# amp_v2.net
KiCad netlist of a schematic drawn in Altium Designer
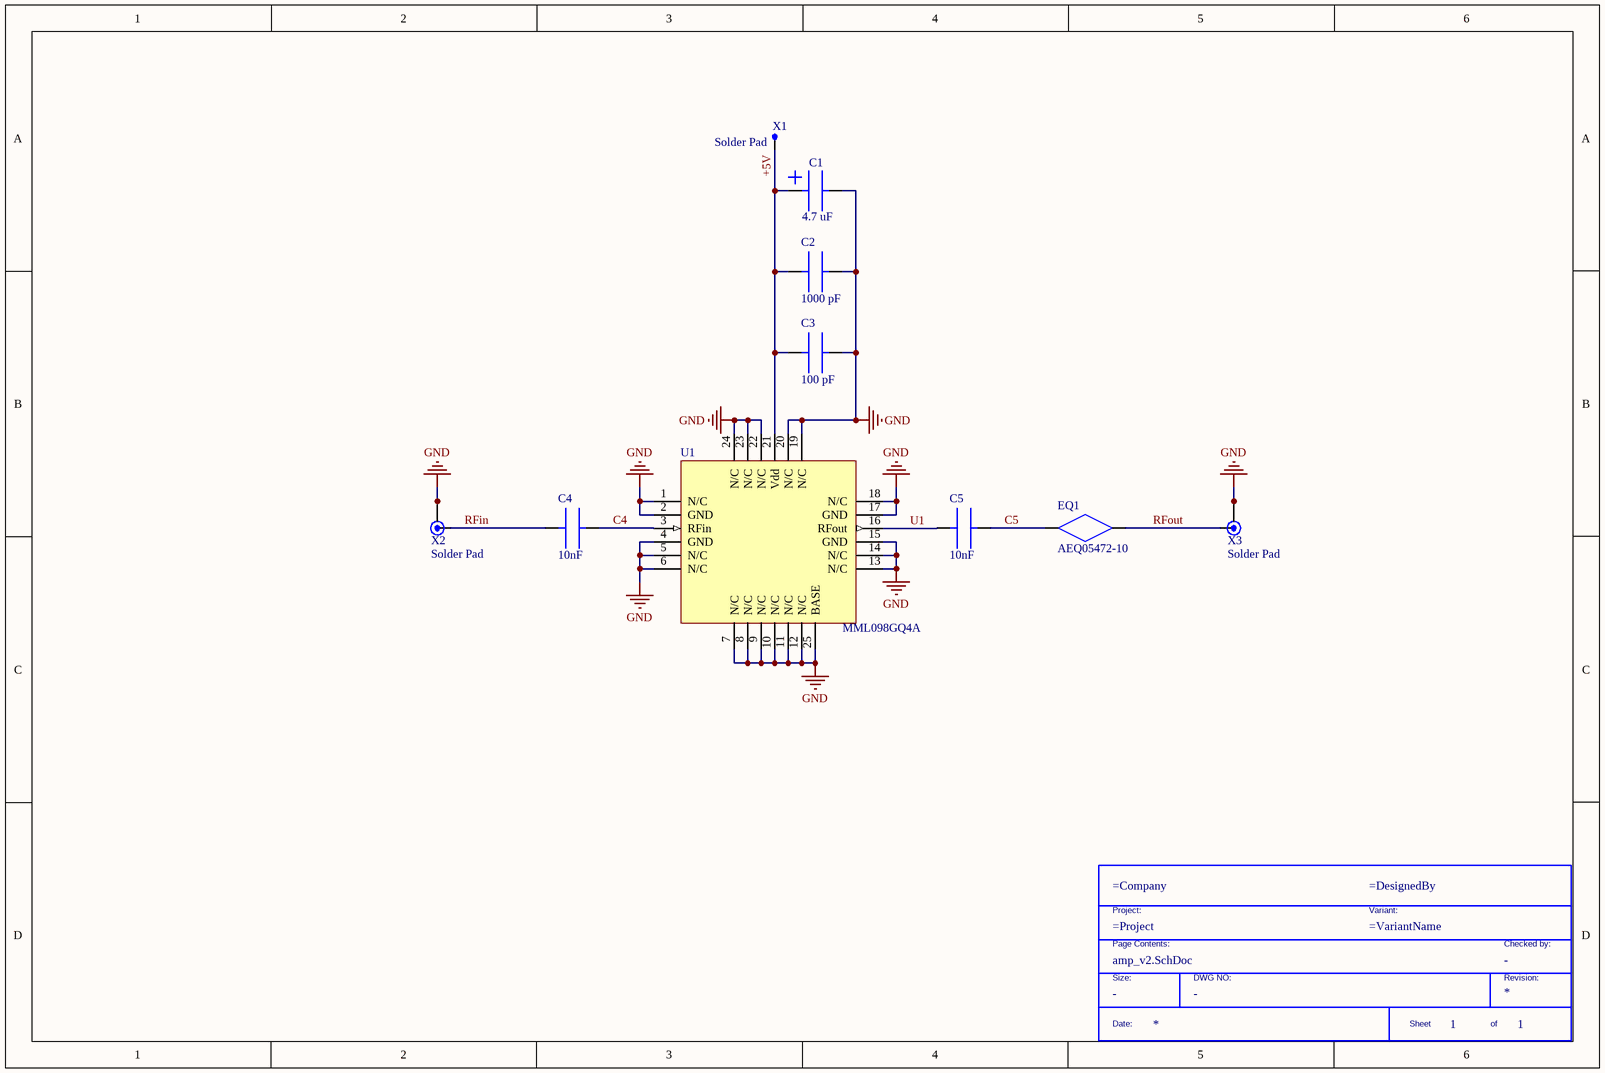
[diagram p0: amp_v2.SchDoc]

(export (version "E")
  (design (tool "Eeschema 10.0.6"))
  (components
    (comp (ref "*")
      (value "TitleBlock")
      (description "Standard Title Block")
      (fields (field (name "DWG NO") "-") (field (name "SIZE") "-") (field (name "CHECKED BY") "-"))
      (libsource (lib "amp") (part "TitleBlock"))
    )
    (comp (ref "C1")
      (value "4.7 uF")
      (footprint "C4_7uF")
      (fields
        (field (name "MANUFACTURER") "Vishay Sprague")
        (field (name "MANUFACTURER PART NUMBER") "TH3A475K010C2900")
      )
      (libsource (lib "amp") (part "C7_4uF_TH3A475K010C2900"))
    )
    (comp (ref "C2")
      (value "1000 pF")
      (footprint "C1000pF__C100nF")
      (fields
        (field (name "MANUFACTURER") "Murata")
        (field (name "MANUFACTURER PART NUMBER") "GCM1885C1H102FA16D")
      )
      (libsource (lib "amp") (part "C1000pF_GCM1885C1H102FA16D"))
    )
    (comp (ref "C3")
      (value "100 pF")
      (footprint "C100pF")
      (description "Multilayer Ceramic Capacitors MLCC - SMD/SMT 100 pF 100 VDC 1% 0402 C0G (NP0)")
      (fields
        (field (name "MANUFACTURER") "Murata")
        (field (name "MANUFACTURER PART NUMBER") "GRM1555C2A101FA01D")
      )
      (libsource (lib "amp") (part "C100pF_GRM1555C2A101FA01D"))
    )
    (comp (ref "C4")
      (value "10nF")
      (footprint "C10nF")
      (fields (field (name "MANUFACTURER") "Murata") (field (name "MANUFACTURER PART NUMBER") "939113733510"))
      (libsource (lib "amp") (part "C10nF_939113733510"))
    )
    (comp (ref "C5")
      (value "10nF")
      (footprint "C10nF")
      (fields (field (name "MANUFACTURER") "Murata") (field (name "MANUFACTURER PART NUMBER") "939113733510"))
      (libsource (lib "amp") (part "C10nF_939113733510"))
    )
    (comp (ref "EQ1")
      (value "AEQ05472-10")
      (footprint "EQ_AEQ05472")
      (description "Rf Filter Gain Equalizer 2SMD")
      (fields (field (name "MANUFACTURER") "Knowles Dielectric Labs"))
      (libsource (lib "amp") (part "EQ_AEQ05472-10"))
    )
    (comp (ref "U1")
      (value "MML098GQ4A")
      (footprint "amp_MML098GQ4A")
      (libsource (lib "amp") (part "amp_MML098GQ4A"))
    )
    (comp (ref "X1")
      (value "Solder Pad")
      (footprint "Solder Pad")
      (description "Pad to solder wires to")
      (libsource (lib "amp") (part "Solder Pad"))
    )
    (comp (ref "X2")
      (value "Solder Pad")
      (footprint "CPW Edge Connector")
      (description "Solder pad for RF Coplanar Waveguide Rogers 4350B Thickness 0.020\" Copper 1oz")
      (libsource (lib "amp") (part "RF  CPW Solder Pad"))
    )
    (comp (ref "X3")
      (value "Solder Pad")
      (footprint "CPW Edge Connector")
      (description "Solder pad for RF Coplanar Waveguide Rogers 4350B Thickness 0.020\" Copper 1oz")
      (libsource (lib "amp") (part "RF  CPW Solder Pad"))
    )
  )
  (nets
    (net (code "1") (name "/+5V") (class "Default")
      (node (ref "C1") (pin "1") (pinfunction "+_1") (pintype "passive"))
      (node (ref "C2") (pin "1") (pinfunction "1_1") (pintype "passive"))
      (node (ref "C3") (pin "1") (pinfunction "1_1") (pintype "passive"))
      (node (ref "U1") (pin "21") (pinfunction "Vdd_21") (pintype "power_in"))
      (node (ref "X1") (pin "1") (pinfunction "1_1") (pintype "passive"))
    )
    (net (code "2") (name "/C4") (class "Default")
      (node (ref "C4") (pin "2") (pinfunction "2_2") (pintype "passive"))
      (node (ref "U1") (pin "3") (pinfunction "RFin_3") (pintype "input"))
    )
    (net (code "3") (name "/C5") (class "Default")
      (node (ref "C5") (pin "2") (pinfunction "2_2") (pintype "passive"))
      (node (ref "EQ1") (pin "1") (pinfunction "1_1") (pintype "passive"))
    )
    (net (code "4") (name "/RFin") (class "Default")
      (node (ref "C4") (pin "1") (pinfunction "1_1") (pintype "passive"))
      (node (ref "X2") (pin "1") (pinfunction "1_1") (pintype "passive"))
    )
    (net (code "5") (name "/RFout") (class "Default")
      (node (ref "EQ1") (pin "2") (pinfunction "2_2") (pintype "passive"))
      (node (ref "X3") (pin "1") (pinfunction "1_1") (pintype "passive"))
    )
    (net (code "6") (name "/U1") (class "Default")
      (node (ref "C5") (pin "1") (pinfunction "1_1") (pintype "passive"))
      (node (ref "U1") (pin "16") (pinfunction "RFout_16") (pintype "output"))
    )
    (net (code "7") (name "GND") (class "Default")
      (node (ref "C1") (pin "2") (pinfunction "2_2") (pintype "passive"))
      (node (ref "C2") (pin "2") (pinfunction "2_2") (pintype "passive"))
      (node (ref "C3") (pin "2") (pinfunction "2_2") (pintype "passive"))
      (node (ref "U1") (pin "1") (pinfunction "N/C_1") (pintype "passive"))
      (node (ref "U1") (pin "10") (pinfunction "N/C_10") (pintype "passive"))
      (node (ref "U1") (pin "11") (pinfunction "N/C_11") (pintype "passive"))
      (node (ref "U1") (pin "12") (pinfunction "N/C_12") (pintype "passive"))
      (node (ref "U1") (pin "13") (pinfunction "N/C_13") (pintype "passive"))
      (node (ref "U1") (pin "14") (pinfunction "N/C_14") (pintype "passive"))
      (node (ref "U1") (pin "15") (pinfunction "GND_15") (pintype "power_in"))
      (node (ref "U1") (pin "17") (pinfunction "GND_17") (pintype "power_in"))
      (node (ref "U1") (pin "18") (pinfunction "N/C_18") (pintype "passive"))
      (node (ref "U1") (pin "19") (pinfunction "N/C_19") (pintype "passive"))
      (node (ref "U1") (pin "2") (pinfunction "GND_2") (pintype "power_in"))
      (node (ref "U1") (pin "20") (pinfunction "N/C_20") (pintype "passive"))
      (node (ref "U1") (pin "22") (pinfunction "N/C_22") (pintype "passive"))
      (node (ref "U1") (pin "23") (pinfunction "N/C_23") (pintype "passive"))
      (node (ref "U1") (pin "24") (pinfunction "N/C_24") (pintype "passive"))
      (node (ref "U1") (pin "25") (pinfunction "BASE_25") (pintype "power_in"))
      (node (ref "U1") (pin "4") (pinfunction "GND_4") (pintype "power_in"))
      (node (ref "U1") (pin "5") (pinfunction "N/C_5") (pintype "passive"))
      (node (ref "U1") (pin "6") (pinfunction "N/C_6") (pintype "passive"))
      (node (ref "U1") (pin "7") (pinfunction "N/C_7") (pintype "passive"))
      (node (ref "U1") (pin "8") (pinfunction "N/C_8") (pintype "passive"))
      (node (ref "U1") (pin "9") (pinfunction "N/C_9") (pintype "passive"))
      (node (ref "X2") (pin "2") (pinfunction "2_2") (pintype "passive"))
      (node (ref "X2") (pin "3") (pinfunction "3_3") (pintype "passive"))
      (node (ref "X3") (pin "2") (pinfunction "2_2") (pintype "passive"))
      (node (ref "X3") (pin "3") (pinfunction "3_3") (pintype "passive"))
    )
  )
)
